# rfidreceiver.net
KiCad netlist of a schematic drawn in EAGLE
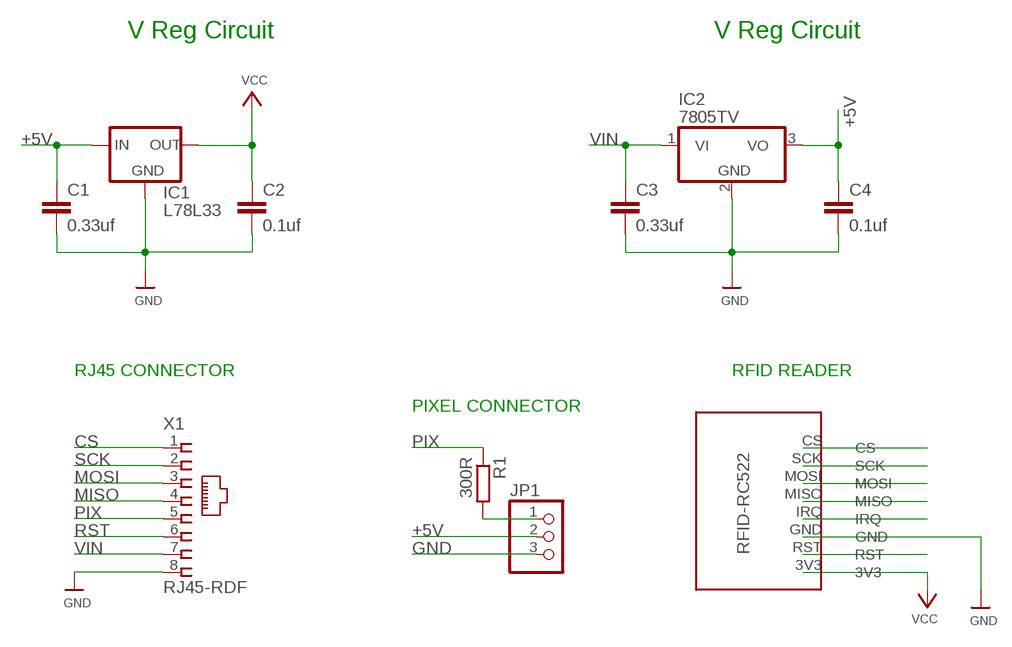
[diagram p0: schematic, sheet 1]

(export (version "E")
  (design (tool "Eeschema 10.0.6"))
  (components
    (comp (ref "C1")
      (value "0.33uf")
      (footprint "eagle-import:C050-024X044")
      (libsource (lib "eagle-import") (part "C-EU050-024X044"))
    )
    (comp (ref "C2")
      (value "0.1uf")
      (footprint "eagle-import:C050-024X044")
      (libsource (lib "eagle-import") (part "C-EU050-024X044"))
    )
    (comp (ref "C3")
      (value "0.33uf")
      (footprint "eagle-import:C050-024X044")
      (libsource (lib "eagle-import") (part "C-EU050-024X044"))
    )
    (comp (ref "C4")
      (value "0.1uf")
      (footprint "eagle-import:C050-024X044")
      (libsource (lib "eagle-import") (part "C-EU050-024X044"))
    )
    (comp (ref "IC1")
      (value "L78L33")
      (footprint "eagle-import:TO92-INLINE")
      (libsource (lib "eagle-import") (part "MCP1700L78L33PINS"))
    )
    (comp (ref "IC2")
      (value "7805TV")
      (footprint "eagle-import:TO220V")
      (libsource (lib "eagle-import") (part "78TV05"))
    )
    (comp (ref "JP1")
      (value "PINHD-1X3CB")
      (footprint "eagle-import:1X03-CLEANBIG")
      (libsource (lib "eagle-import") (part "PINHD-1X3CB"))
    )
    (comp (ref "R1")
      (value "300R")
      (footprint "eagle-import:0204_5")
      (libsource (lib "eagle-import") (part "R-EU_0204/5"))
    )
    (comp (ref "U$2")
      (value "RFID-RC522")
      (footprint "eagle-import:RFID-RC522")
      (libsource (lib "eagle-import") (part "RFID-RC522"))
    )
    (comp (ref "X1")
      (value "RJ45-RDF")
      (footprint "eagle-import:RJ45-RDF")
      (libsource (lib "eagle-import") (part "RJ45-RDF"))
    )
  )
  (nets
    (net (code "1") (name "/+5V") (class "Default")
      (node (ref "C1") (pin "1") (pinfunction "1_1") (pintype "passive"))
      (node (ref "C4") (pin "1") (pinfunction "1_1") (pintype "passive"))
      (node (ref "IC1") (pin "1") (pinfunction "IN_1") (pintype "input"))
      (node (ref "IC2") (pin "3") (pinfunction "VO_3") (pintype "passive"))
      (node (ref "JP1") (pin "2") (pinfunction "2_2") (pintype "passive"))
    )
    (net (code "2") (name "/CS") (class "Default")
      (node (ref "U$2") (pin "CS") (pinfunction "CS_CS") (pintype "bidirectional"))
      (node (ref "X1") (pin "1") (pinfunction "1_1") (pintype "passive"))
    )
    (net (code "3") (name "/MISO") (class "Default")
      (node (ref "U$2") (pin "MISO") (pinfunction "MISO_MISO") (pintype "bidirectional"))
      (node (ref "X1") (pin "4") (pinfunction "4_4") (pintype "passive"))
    )
    (net (code "4") (name "/MOSI") (class "Default")
      (node (ref "U$2") (pin "MOSI") (pinfunction "MOSI_MOSI") (pintype "bidirectional"))
      (node (ref "X1") (pin "3") (pinfunction "3_3") (pintype "passive"))
    )
    (net (code "5") (name "/PIX") (class "Default")
      (node (ref "R1") (pin "1") (pinfunction "1_1") (pintype "passive"))
      (node (ref "X1") (pin "5") (pinfunction "5_5") (pintype "passive"))
    )
    (net (code "6") (name "/RST") (class "Default")
      (node (ref "U$2") (pin "RST") (pinfunction "RST_RST") (pintype "bidirectional"))
      (node (ref "X1") (pin "6") (pinfunction "6_6") (pintype "passive"))
    )
    (net (code "7") (name "/SCK") (class "Default")
      (node (ref "U$2") (pin "SCK") (pinfunction "SCK_SCK") (pintype "bidirectional"))
      (node (ref "X1") (pin "2") (pinfunction "2_2") (pintype "passive"))
    )
    (net (code "8") (name "/VIN") (class "Default")
      (node (ref "C3") (pin "1") (pinfunction "1_1") (pintype "passive"))
      (node (ref "IC2") (pin "1") (pinfunction "VI_1") (pintype "input"))
      (node (ref "X1") (pin "7") (pinfunction "7_7") (pintype "passive"))
    )
    (net (code "9") (name "GND") (class "Default")
      (node (ref "C1") (pin "2") (pinfunction "2_2") (pintype "passive"))
      (node (ref "C2") (pin "2") (pinfunction "2_2") (pintype "passive"))
      (node (ref "C3") (pin "2") (pinfunction "2_2") (pintype "passive"))
      (node (ref "C4") (pin "2") (pinfunction "2_2") (pintype "passive"))
      (node (ref "IC1") (pin "2") (pinfunction "GND_2") (pintype "input"))
      (node (ref "IC2") (pin "2") (pinfunction "GND_2") (pintype "passive"))
      (node (ref "JP1") (pin "3") (pinfunction "3_3") (pintype "passive"))
      (node (ref "U$2") (pin "GND") (pinfunction "GND_GND") (pintype "bidirectional"))
      (node (ref "X1") (pin "8") (pinfunction "8_8") (pintype "passive"))
    )
    (net (code "10") (name "Net-(JP1-Pad1)") (class "Default")
      (node (ref "JP1") (pin "1") (pinfunction "1_1") (pintype "passive"))
      (node (ref "R1") (pin "2") (pinfunction "2_2") (pintype "passive"))
    )
    (net (code "11") (name "VCC") (class "Default")
      (node (ref "C2") (pin "1") (pinfunction "1_1") (pintype "passive"))
      (node (ref "IC1") (pin "3") (pinfunction "OUT_3") (pintype "passive"))
      (node (ref "U$2") (pin "3V3") (pinfunction "3V3_3V3") (pintype "bidirectional"))
    )
    (net (code "12") (name "unconnected-(U$2-PadIRQ)") (class "Default")
      (node (ref "U$2") (pin "IRQ") (pinfunction "IRQ_IRQ") (pintype "bidirectional"))
    )
  )
)
